# CW340_HyperDebug.net
KiCad netlist of a schematic drawn in Altium Designer
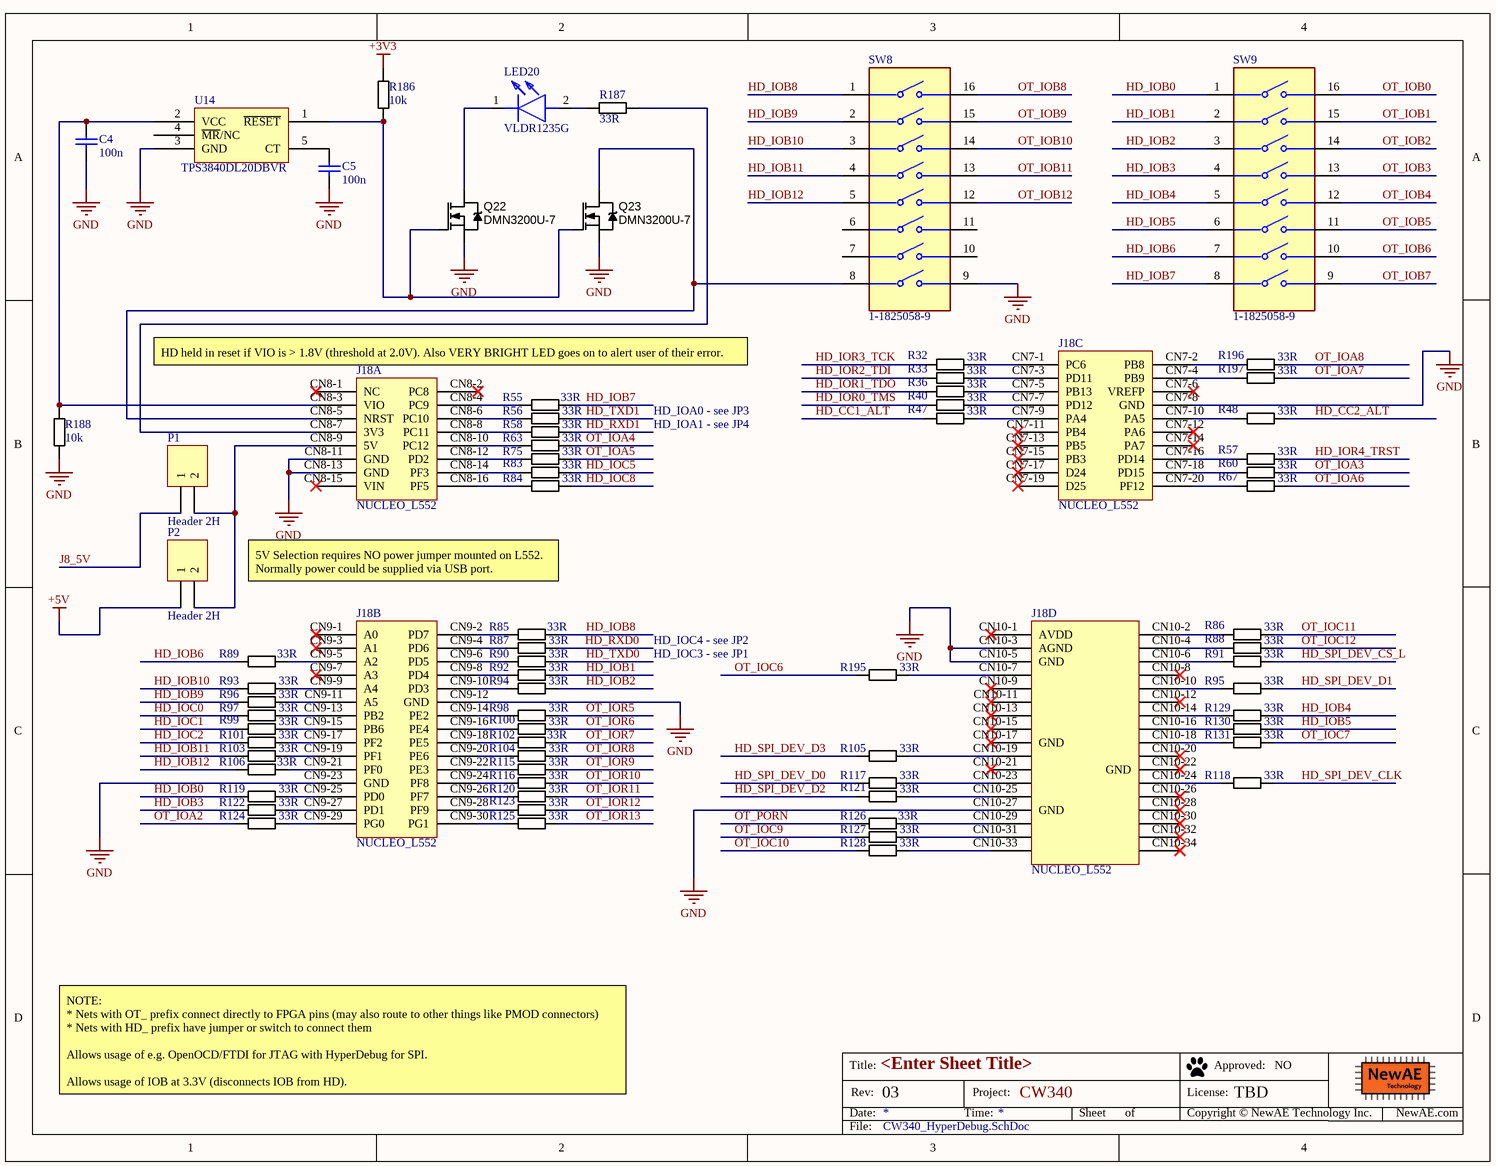
[diagram p0: CW340_HyperDebug.SchDoc]

(export (version "E")
  (design (tool "Eeschema 10.0.6"))
  (components
    (comp (ref "C4")
      (value "100n")
      (footprint "CAPC0402_M")
      (description "100n, 0402")
      (fields (field (name "PART NUMBER") "CCHIP-100n-0402"))
      (libsource (lib "NewAE_AltiumLib") (part "CAP"))
    )
    (comp (ref "C5")
      (value "100n")
      (footprint "CAPC0402_M")
      (description "100n, 0402")
      (fields (field (name "PART NUMBER") "CCHIP-100n-0402"))
      (libsource (lib "NewAE_AltiumLib") (part "CAP"))
    )
    (comp (ref "J18")
      (value "NUCLEO_L552")
      (footprint "NUCLEO-L552ZE")
      (libsource (lib "NewAE_AltiumLib") (part "NUCLEO_L552"))
    )
    (comp (ref "LED20")
      (value "VLDR1235G")
      (footprint "SamacSys:VLDR1235G")
      (description "LED")
      (fields (field (name "MOUSER PART NUMBER") "78-VLDR1235G"))
      (libsource (lib "*") (part "VLDR1235G"))
    )
    (comp (ref "P1")
      (value "Header 2H")
      (footprint "HDR1X2H")
      (description "Header, 2-Pin, Right Angle")
      (fields (field (name "PUBLISHER") "Altium Limited"))
      (libsource (lib "Miscellaneous Connectors") (part "Header 2H"))
    )
    (comp (ref "P2")
      (value "Header 2H")
      (footprint "HDR1X2H")
      (description "Header, 2-Pin, Right Angle")
      (fields (field (name "PUBLISHER") "Altium Limited"))
      (libsource (lib "Miscellaneous Connectors") (part "Header 2H"))
    )
    (comp (ref "Q22")
      (value "DMN3200U-7")
      (footprint "SOT95P245X110-3M")
      (description "MOSFET N-CH 30V 2.2A SOT23-3")
      (libsource (lib "NewAE_AltiumLib") (part "MOSFET_N_GSD"))
    )
    (comp (ref "Q23")
      (value "DMN3200U-7")
      (footprint "SOT95P245X110-3M")
      (description "MOSFET N-CH 30V 2.2A SOT23-3")
      (libsource (lib "NewAE_AltiumLib") (part "MOSFET_N_GSD"))
    )
    (comp (ref "R32")
      (value "33R")
      (footprint "RESC1608X55N")
      (description "33R res, 0603, 1%, 1/10W")
      (fields (field (name "PART NUMBER") "RCHIP-33R-0603") (field (name "TOLERANCE") "1%"))
      (libsource (lib "NewAE_AltiumLib") (part "RES-EU"))
    )
    (comp (ref "R33")
      (value "33R")
      (footprint "RESC1608X55N")
      (description "33R res, 0603, 1%, 1/10W")
      (fields (field (name "PART NUMBER") "RCHIP-33R-0603") (field (name "TOLERANCE") "1%"))
      (libsource (lib "NewAE_AltiumLib") (part "RES-EU"))
    )
    (comp (ref "R36")
      (value "33R")
      (footprint "RESC1608X55N")
      (description "33R res, 0603, 1%, 1/10W")
      (fields (field (name "PART NUMBER") "RCHIP-33R-0603") (field (name "TOLERANCE") "1%"))
      (libsource (lib "NewAE_AltiumLib") (part "RES-EU"))
    )
    (comp (ref "R40")
      (value "33R")
      (footprint "RESC1608X55N")
      (description "33R res, 0603, 1%, 1/10W")
      (fields (field (name "PART NUMBER") "RCHIP-33R-0603") (field (name "TOLERANCE") "1%"))
      (libsource (lib "NewAE_AltiumLib") (part "RES-EU"))
    )
    (comp (ref "R47")
      (value "33R")
      (footprint "RESC1608X55N")
      (description "33R res, 0603, 1%, 1/10W")
      (fields (field (name "PART NUMBER") "RCHIP-33R-0603") (field (name "TOLERANCE") "1%"))
      (libsource (lib "NewAE_AltiumLib") (part "RES-EU"))
    )
    (comp (ref "R48")
      (value "33R")
      (footprint "RESC1608X55N")
      (description "33R res, 0603, 1%, 1/10W")
      (fields (field (name "PART NUMBER") "RCHIP-33R-0603") (field (name "TOLERANCE") "1%"))
      (libsource (lib "NewAE_AltiumLib") (part "RES-EU"))
    )
    (comp (ref "R55")
      (value "33R")
      (footprint "RESC1608X55N")
      (description "33R res, 0603, 1%, 1/10W")
      (fields (field (name "PART NUMBER") "RCHIP-33R-0603") (field (name "TOLERANCE") "1%"))
      (libsource (lib "NewAE_AltiumLib") (part "RES-EU"))
    )
    (comp (ref "R56")
      (value "33R")
      (footprint "RESC1608X55N")
      (description "33R res, 0603, 1%, 1/10W")
      (fields (field (name "PART NUMBER") "RCHIP-33R-0603") (field (name "TOLERANCE") "1%"))
      (libsource (lib "NewAE_AltiumLib") (part "RES-EU"))
    )
    (comp (ref "R57")
      (value "33R")
      (footprint "RESC1608X55N")
      (description "33R res, 0603, 1%, 1/10W")
      (fields (field (name "PART NUMBER") "RCHIP-33R-0603") (field (name "TOLERANCE") "1%"))
      (libsource (lib "NewAE_AltiumLib") (part "RES-EU"))
    )
    (comp (ref "R58")
      (value "33R")
      (footprint "RESC1608X55N")
      (description "33R res, 0603, 1%, 1/10W")
      (fields (field (name "PART NUMBER") "RCHIP-33R-0603") (field (name "TOLERANCE") "1%"))
      (libsource (lib "NewAE_AltiumLib") (part "RES-EU"))
    )
    (comp (ref "R60")
      (value "33R")
      (footprint "RESC1608X55N")
      (description "33R res, 0603, 1%, 1/10W")
      (fields (field (name "PART NUMBER") "RCHIP-33R-0603") (field (name "TOLERANCE") "1%"))
      (libsource (lib "NewAE_AltiumLib") (part "RES-EU"))
    )
    (comp (ref "R63")
      (value "33R")
      (footprint "RESC1608X55N")
      (description "33R res, 0603, 1%, 1/10W")
      (fields (field (name "PART NUMBER") "RCHIP-33R-0603") (field (name "TOLERANCE") "1%"))
      (libsource (lib "NewAE_AltiumLib") (part "RES-EU"))
    )
    (comp (ref "R67")
      (value "33R")
      (footprint "RESC1608X55N")
      (description "33R res, 0603, 1%, 1/10W")
      (fields (field (name "PART NUMBER") "RCHIP-33R-0603") (field (name "TOLERANCE") "1%"))
      (libsource (lib "NewAE_AltiumLib") (part "RES-EU"))
    )
    (comp (ref "R75")
      (value "33R")
      (footprint "RESC1608X55N")
      (description "33R res, 0603, 1%, 1/10W")
      (fields (field (name "PART NUMBER") "RCHIP-33R-0603") (field (name "TOLERANCE") "1%"))
      (libsource (lib "NewAE_AltiumLib") (part "RES-EU"))
    )
    (comp (ref "R83")
      (value "33R")
      (footprint "RESC1608X55N")
      (description "33R res, 0603, 1%, 1/10W")
      (fields (field (name "PART NUMBER") "RCHIP-33R-0603") (field (name "TOLERANCE") "1%"))
      (libsource (lib "NewAE_AltiumLib") (part "RES-EU"))
    )
    (comp (ref "R84")
      (value "33R")
      (footprint "RESC1608X55N")
      (description "33R res, 0603, 1%, 1/10W")
      (fields (field (name "PART NUMBER") "RCHIP-33R-0603") (field (name "TOLERANCE") "1%"))
      (libsource (lib "NewAE_AltiumLib") (part "RES-EU"))
    )
    (comp (ref "R85")
      (value "33R")
      (footprint "RESC1608X55N")
      (description "33R res, 0603, 1%, 1/10W")
      (fields (field (name "PART NUMBER") "RCHIP-33R-0603") (field (name "TOLERANCE") "1%"))
      (libsource (lib "NewAE_AltiumLib") (part "RES-EU"))
    )
    (comp (ref "R86")
      (value "33R")
      (footprint "RESC1608X55N")
      (description "33R res, 0603, 1%, 1/10W")
      (fields (field (name "PART NUMBER") "RCHIP-33R-0603") (field (name "TOLERANCE") "1%"))
      (libsource (lib "NewAE_AltiumLib") (part "RES-EU"))
    )
    (comp (ref "R87")
      (value "33R")
      (footprint "RESC1608X55N")
      (description "33R res, 0603, 1%, 1/10W")
      (fields (field (name "PART NUMBER") "RCHIP-33R-0603") (field (name "TOLERANCE") "1%"))
      (libsource (lib "NewAE_AltiumLib") (part "RES-EU"))
    )
    (comp (ref "R88")
      (value "33R")
      (footprint "RESC1608X55N")
      (description "33R res, 0603, 1%, 1/10W")
      (fields (field (name "PART NUMBER") "RCHIP-33R-0603") (field (name "TOLERANCE") "1%"))
      (libsource (lib "NewAE_AltiumLib") (part "RES-EU"))
    )
    (comp (ref "R89")
      (value "33R")
      (footprint "RESC1608X55N")
      (description "33R res, 0603, 1%, 1/10W")
      (fields (field (name "PART NUMBER") "RCHIP-33R-0603") (field (name "TOLERANCE") "1%"))
      (libsource (lib "NewAE_AltiumLib") (part "RES-EU"))
    )
    (comp (ref "R90")
      (value "33R")
      (footprint "RESC1608X55N")
      (description "33R res, 0603, 1%, 1/10W")
      (fields (field (name "PART NUMBER") "RCHIP-33R-0603") (field (name "TOLERANCE") "1%"))
      (libsource (lib "NewAE_AltiumLib") (part "RES-EU"))
    )
    (comp (ref "R91")
      (value "33R")
      (footprint "RESC1608X55N")
      (description "33R res, 0603, 1%, 1/10W")
      (fields (field (name "PART NUMBER") "RCHIP-33R-0603") (field (name "TOLERANCE") "1%"))
      (libsource (lib "NewAE_AltiumLib") (part "RES-EU"))
    )
    (comp (ref "R92")
      (value "33R")
      (footprint "RESC1608X55N")
      (description "33R res, 0603, 1%, 1/10W")
      (fields (field (name "PART NUMBER") "RCHIP-33R-0603") (field (name "TOLERANCE") "1%"))
      (libsource (lib "NewAE_AltiumLib") (part "RES-EU"))
    )
    (comp (ref "R93")
      (value "33R")
      (footprint "RESC1608X55N")
      (description "33R res, 0603, 1%, 1/10W")
      (fields (field (name "PART NUMBER") "RCHIP-33R-0603") (field (name "TOLERANCE") "1%"))
      (libsource (lib "NewAE_AltiumLib") (part "RES-EU"))
    )
    (comp (ref "R94")
      (value "33R")
      (footprint "RESC1608X55N")
      (description "33R res, 0603, 1%, 1/10W")
      (fields (field (name "PART NUMBER") "RCHIP-33R-0603") (field (name "TOLERANCE") "1%"))
      (libsource (lib "NewAE_AltiumLib") (part "RES-EU"))
    )
    (comp (ref "R95")
      (value "33R")
      (footprint "RESC1608X55N")
      (description "33R res, 0603, 1%, 1/10W")
      (fields (field (name "PART NUMBER") "RCHIP-33R-0603") (field (name "TOLERANCE") "1%"))
      (libsource (lib "NewAE_AltiumLib") (part "RES-EU"))
    )
    (comp (ref "R96")
      (value "33R")
      (footprint "RESC1608X55N")
      (description "33R res, 0603, 1%, 1/10W")
      (fields (field (name "PART NUMBER") "RCHIP-33R-0603") (field (name "TOLERANCE") "1%"))
      (libsource (lib "NewAE_AltiumLib") (part "RES-EU"))
    )
    (comp (ref "R97")
      (value "33R")
      (footprint "RESC1608X55N")
      (description "33R res, 0603, 1%, 1/10W")
      (fields (field (name "PART NUMBER") "RCHIP-33R-0603") (field (name "TOLERANCE") "1%"))
      (libsource (lib "NewAE_AltiumLib") (part "RES-EU"))
    )
    (comp (ref "R98")
      (value "33R")
      (footprint "RESC1608X55N")
      (description "33R res, 0603, 1%, 1/10W")
      (fields (field (name "PART NUMBER") "RCHIP-33R-0603") (field (name "TOLERANCE") "1%"))
      (libsource (lib "NewAE_AltiumLib") (part "RES-EU"))
    )
    (comp (ref "R99")
      (value "33R")
      (footprint "RESC1608X55N")
      (description "33R res, 0603, 1%, 1/10W")
      (fields (field (name "PART NUMBER") "RCHIP-33R-0603") (field (name "TOLERANCE") "1%"))
      (libsource (lib "NewAE_AltiumLib") (part "RES-EU"))
    )
    (comp (ref "R100")
      (value "33R")
      (footprint "RESC1608X55N")
      (description "33R res, 0603, 1%, 1/10W")
      (fields (field (name "PART NUMBER") "RCHIP-33R-0603") (field (name "TOLERANCE") "1%"))
      (libsource (lib "NewAE_AltiumLib") (part "RES-EU"))
    )
    (comp (ref "R101")
      (value "33R")
      (footprint "RESC1608X55N")
      (description "33R res, 0603, 1%, 1/10W")
      (fields (field (name "PART NUMBER") "RCHIP-33R-0603") (field (name "TOLERANCE") "1%"))
      (libsource (lib "NewAE_AltiumLib") (part "RES-EU"))
    )
    (comp (ref "R102")
      (value "33R")
      (footprint "RESC1608X55N")
      (description "33R res, 0603, 1%, 1/10W")
      (fields (field (name "PART NUMBER") "RCHIP-33R-0603") (field (name "TOLERANCE") "1%"))
      (libsource (lib "NewAE_AltiumLib") (part "RES-EU"))
    )
    (comp (ref "R103")
      (value "33R")
      (footprint "RESC1608X55N")
      (description "33R res, 0603, 1%, 1/10W")
      (fields (field (name "PART NUMBER") "RCHIP-33R-0603") (field (name "TOLERANCE") "1%"))
      (libsource (lib "NewAE_AltiumLib") (part "RES-EU"))
    )
    (comp (ref "R104")
      (value "33R")
      (footprint "RESC1608X55N")
      (description "33R res, 0603, 1%, 1/10W")
      (fields (field (name "PART NUMBER") "RCHIP-33R-0603") (field (name "TOLERANCE") "1%"))
      (libsource (lib "NewAE_AltiumLib") (part "RES-EU"))
    )
    (comp (ref "R105")
      (value "33R")
      (footprint "RESC1608X55N")
      (description "33R res, 0603, 1%, 1/10W")
      (fields (field (name "PART NUMBER") "RCHIP-33R-0603") (field (name "TOLERANCE") "1%"))
      (libsource (lib "NewAE_AltiumLib") (part "RES-EU"))
    )
    (comp (ref "R106")
      (value "33R")
      (footprint "RESC1608X55N")
      (description "33R res, 0603, 1%, 1/10W")
      (fields (field (name "PART NUMBER") "RCHIP-33R-0603") (field (name "TOLERANCE") "1%"))
      (libsource (lib "NewAE_AltiumLib") (part "RES-EU"))
    )
    (comp (ref "R115")
      (value "33R")
      (footprint "RESC1608X55N")
      (description "33R res, 0603, 1%, 1/10W")
      (fields (field (name "PART NUMBER") "RCHIP-33R-0603") (field (name "TOLERANCE") "1%"))
      (libsource (lib "NewAE_AltiumLib") (part "RES-EU"))
    )
    (comp (ref "R116")
      (value "33R")
      (footprint "RESC1608X55N")
      (description "33R res, 0603, 1%, 1/10W")
      (fields (field (name "PART NUMBER") "RCHIP-33R-0603") (field (name "TOLERANCE") "1%"))
      (libsource (lib "NewAE_AltiumLib") (part "RES-EU"))
    )
    (comp (ref "R117")
      (value "33R")
      (footprint "RESC1608X55N")
      (description "33R res, 0603, 1%, 1/10W")
      (fields (field (name "PART NUMBER") "RCHIP-33R-0603") (field (name "TOLERANCE") "1%"))
      (libsource (lib "NewAE_AltiumLib") (part "RES-EU"))
    )
    (comp (ref "R118")
      (value "33R")
      (footprint "RESC1608X55N")
      (description "33R res, 0603, 1%, 1/10W")
      (fields (field (name "PART NUMBER") "RCHIP-33R-0603") (field (name "TOLERANCE") "1%"))
      (libsource (lib "NewAE_AltiumLib") (part "RES-EU"))
    )
    (comp (ref "R119")
      (value "33R")
      (footprint "RESC1608X55N")
      (description "33R res, 0603, 1%, 1/10W")
      (fields (field (name "PART NUMBER") "RCHIP-33R-0603") (field (name "TOLERANCE") "1%"))
      (libsource (lib "NewAE_AltiumLib") (part "RES-EU"))
    )
    (comp (ref "R120")
      (value "33R")
      (footprint "RESC1608X55N")
      (description "33R res, 0603, 1%, 1/10W")
      (fields (field (name "PART NUMBER") "RCHIP-33R-0603") (field (name "TOLERANCE") "1%"))
      (libsource (lib "NewAE_AltiumLib") (part "RES-EU"))
    )
    (comp (ref "R121")
      (value "33R")
      (footprint "RESC1608X55N")
      (description "33R res, 0603, 1%, 1/10W")
      (fields (field (name "PART NUMBER") "RCHIP-33R-0603") (field (name "TOLERANCE") "1%"))
      (libsource (lib "NewAE_AltiumLib") (part "RES-EU"))
    )
    (comp (ref "R122")
      (value "33R")
      (footprint "RESC1608X55N")
      (description "33R res, 0603, 1%, 1/10W")
      (fields (field (name "PART NUMBER") "RCHIP-33R-0603") (field (name "TOLERANCE") "1%"))
      (libsource (lib "NewAE_AltiumLib") (part "RES-EU"))
    )
    (comp (ref "R123")
      (value "33R")
      (footprint "RESC1608X55N")
      (description "33R res, 0603, 1%, 1/10W")
      (fields (field (name "PART NUMBER") "RCHIP-33R-0603") (field (name "TOLERANCE") "1%"))
      (libsource (lib "NewAE_AltiumLib") (part "RES-EU"))
    )
    (comp (ref "R124")
      (value "33R")
      (footprint "RESC1608X55N")
      (description "33R res, 0603, 1%, 1/10W")
      (fields (field (name "PART NUMBER") "RCHIP-33R-0603") (field (name "TOLERANCE") "1%"))
      (libsource (lib "NewAE_AltiumLib") (part "RES-EU"))
    )
    (comp (ref "R125")
      (value "33R")
      (footprint "RESC1608X55N")
      (description "33R res, 0603, 1%, 1/10W")
      (fields (field (name "PART NUMBER") "RCHIP-33R-0603") (field (name "TOLERANCE") "1%"))
      (libsource (lib "NewAE_AltiumLib") (part "RES-EU"))
    )
    (comp (ref "R126")
      (value "33R")
      (footprint "RESC1608X55N")
      (description "33R res, 0603, 1%, 1/10W")
      (fields (field (name "PART NUMBER") "RCHIP-33R-0603") (field (name "TOLERANCE") "1%"))
      (libsource (lib "NewAE_AltiumLib") (part "RES-EU"))
    )
    (comp (ref "R127")
      (value "33R")
      (footprint "RESC1608X55N")
      (description "33R res, 0603, 1%, 1/10W")
      (fields (field (name "PART NUMBER") "RCHIP-33R-0603") (field (name "TOLERANCE") "1%"))
      (libsource (lib "NewAE_AltiumLib") (part "RES-EU"))
    )
    (comp (ref "R128")
      (value "33R")
      (footprint "RESC1608X55N")
      (description "33R res, 0603, 1%, 1/10W")
      (fields (field (name "PART NUMBER") "RCHIP-33R-0603") (field (name "TOLERANCE") "1%"))
      (libsource (lib "NewAE_AltiumLib") (part "RES-EU"))
    )
    (comp (ref "R129")
      (value "33R")
      (footprint "RESC1608X55N")
      (description "33R res, 0603, 1%, 1/10W")
      (fields (field (name "PART NUMBER") "RCHIP-33R-0603") (field (name "TOLERANCE") "1%"))
      (libsource (lib "NewAE_AltiumLib") (part "RES-EU"))
    )
    (comp (ref "R130")
      (value "33R")
      (footprint "RESC1608X55N")
      (description "33R res, 0603, 1%, 1/10W")
      (fields (field (name "PART NUMBER") "RCHIP-33R-0603") (field (name "TOLERANCE") "1%"))
      (libsource (lib "NewAE_AltiumLib") (part "RES-EU"))
    )
    (comp (ref "R131")
      (value "33R")
      (footprint "RESC1608X55N")
      (description "33R res, 0603, 1%, 1/10W")
      (fields (field (name "PART NUMBER") "RCHIP-33R-0603") (field (name "TOLERANCE") "1%"))
      (libsource (lib "NewAE_AltiumLib") (part "RES-EU"))
    )
    (comp (ref "R186")
      (value "10k")
      (footprint "RESC1005X40N")
      (description "10k res, 0402, 1%, 1/16W")
      (fields (field (name "PART NUMBER") "RCHIP-10K-0402") (field (name "TOLERANCE") "1%"))
      (libsource (lib "") (part "RES-EU_1"))
    )
    (comp (ref "R187")
      (value "33R")
      (footprint "RESC1608X55N")
      (description "33R res, 0603, 1%, 1/10W")
      (fields (field (name "PART NUMBER") "RCHIP-33R-0603") (field (name "TOLERANCE") "1%"))
      (libsource (lib "NewAE_AltiumLib") (part "RES-EU"))
    )
    (comp (ref "R188")
      (value "10k")
      (footprint "RESC1005X40N")
      (description "10k res, 0402, 1%, 1/16W")
      (fields (field (name "PART NUMBER") "RCHIP-10K-0402") (field (name "TOLERANCE") "1%"))
      (libsource (lib "") (part "RES-EU_1"))
    )
    (comp (ref "R195")
      (value "33R")
      (footprint "RESC1608X55N")
      (description "33R res, 0603, 1%, 1/10W")
      (fields (field (name "PART NUMBER") "RCHIP-33R-0603") (field (name "TOLERANCE") "1%"))
      (libsource (lib "NewAE_AltiumLib") (part "RES-EU"))
    )
    (comp (ref "R196")
      (value "33R")
      (footprint "RESC1608X55N")
      (description "33R res, 0603, 1%, 1/10W")
      (fields (field (name "PART NUMBER") "RCHIP-33R-0603") (field (name "TOLERANCE") "1%"))
      (libsource (lib "NewAE_AltiumLib") (part "RES-EU"))
    )
    (comp (ref "R197")
      (value "33R")
      (footprint "RESC1608X55N")
      (description "33R res, 0603, 1%, 1/10W")
      (fields (field (name "PART NUMBER") "RCHIP-33R-0603") (field (name "TOLERANCE") "1%"))
      (libsource (lib "NewAE_AltiumLib") (part "RES-EU"))
    )
    (comp (ref "SW8")
      (value "1-1825058-9")
      (footprint "FP-1-1825058-9-MFG")
      (description "SWITCH SLIDE DIP SPST 100MA 24V")
      (fields
        (field (name "MANUFACTURER") "TE Connectivity")
        (field (name "OCTOPART") "https://octopart.com/1-1825058-9-te+connectivity-46507285")
      )
      (libsource (lib "Altium Content Vault") (part "88b473189f0daa5e8e83a09a3141fee"))
    )
    (comp (ref "SW9")
      (value "1-1825058-9")
      (footprint "FP-1-1825058-9-MFG")
      (description "SWITCH SLIDE DIP SPST 100MA 24V")
      (fields
        (field (name "MANUFACTURER") "TE Connectivity")
        (field (name "OCTOPART") "https://octopart.com/1-1825058-9-te+connectivity-46507285")
      )
      (libsource (lib "Altium Content Vault") (part "88b473189f0daa5e8e83a09a3141fee"))
    )
    (comp (ref "U14")
      (value "TPS3840DL20DBVR")
      (footprint "SOT23-5P95_285X145L45X40")
      (description "Reset Supervisor")
      (libsource (lib "NewAE_AltiumLib") (part "TPS3840DL"))
    )
  )
  (nets
    (net (code "1") (name "+3V3") (class "Default")
      (node (ref "R186") (pin "1") (pinfunction "1_1") (pintype "passive"))
    )
    (net (code "2") (name "+5V") (class "Default")
      (node (ref "P2") (pin "1") (pinfunction "1_1") (pintype "passive"))
    )
    (net (code "3") (name "/HD_CC1_ALT") (class "Default")
      (node (ref "R47") (pin "1") (pinfunction "1_1") (pintype "passive"))
    )
    (net (code "4") (name "/HD_CC2_ALT") (class "Default")
      (node (ref "R48") (pin "2") (pinfunction "2_2") (pintype "passive"))
    )
    (net (code "5") (name "/HD_IOB0") (class "Default")
      (node (ref "R119") (pin "1") (pinfunction "1_1") (pintype "passive"))
      (node (ref "SW9") (pin "1") (pinfunction "1_1") (pintype "passive"))
    )
    (net (code "6") (name "/HD_IOB1") (class "Default")
      (node (ref "R92") (pin "2") (pinfunction "2_2") (pintype "passive"))
      (node (ref "SW9") (pin "2") (pinfunction "2_2") (pintype "passive"))
    )
    (net (code "7") (name "/HD_IOB2") (class "Default")
      (node (ref "R94") (pin "2") (pinfunction "2_2") (pintype "passive"))
      (node (ref "SW9") (pin "3") (pinfunction "3_3") (pintype "passive"))
    )
    (net (code "8") (name "/HD_IOB3") (class "Default")
      (node (ref "R122") (pin "1") (pinfunction "1_1") (pintype "passive"))
      (node (ref "SW9") (pin "4") (pinfunction "4_4") (pintype "passive"))
    )
    (net (code "9") (name "/HD_IOB4") (class "Default")
      (node (ref "R129") (pin "2") (pinfunction "2_2") (pintype "passive"))
      (node (ref "SW9") (pin "5") (pinfunction "5_5") (pintype "passive"))
    )
    (net (code "10") (name "/HD_IOB5") (class "Default")
      (node (ref "R130") (pin "2") (pinfunction "2_2") (pintype "passive"))
      (node (ref "SW9") (pin "6") (pinfunction "6_6") (pintype "passive"))
    )
    (net (code "11") (name "/HD_IOB6") (class "Default")
      (node (ref "R89") (pin "1") (pinfunction "1_1") (pintype "passive"))
      (node (ref "SW9") (pin "7") (pinfunction "7_7") (pintype "passive"))
    )
    (net (code "12") (name "/HD_IOB7") (class "Default")
      (node (ref "R55") (pin "2") (pinfunction "2_2") (pintype "passive"))
      (node (ref "SW9") (pin "8") (pinfunction "8_8") (pintype "passive"))
    )
    (net (code "13") (name "/HD_IOB8") (class "Default")
      (node (ref "R85") (pin "2") (pinfunction "2_2") (pintype "passive"))
      (node (ref "SW8") (pin "1") (pinfunction "1_1") (pintype "passive"))
    )
    (net (code "14") (name "/HD_IOB9") (class "Default")
      (node (ref "R96") (pin "1") (pinfunction "1_1") (pintype "passive"))
      (node (ref "SW8") (pin "2") (pinfunction "2_2") (pintype "passive"))
    )
    (net (code "15") (name "/HD_IOB10") (class "Default")
      (node (ref "R93") (pin "1") (pinfunction "1_1") (pintype "passive"))
      (node (ref "SW8") (pin "3") (pinfunction "3_3") (pintype "passive"))
    )
    (net (code "16") (name "/HD_IOB11") (class "Default")
      (node (ref "R103") (pin "1") (pinfunction "1_1") (pintype "passive"))
      (node (ref "SW8") (pin "4") (pinfunction "4_4") (pintype "passive"))
    )
    (net (code "17") (name "/HD_IOB12") (class "Default")
      (node (ref "R106") (pin "1") (pinfunction "1_1") (pintype "passive"))
      (node (ref "SW8") (pin "5") (pinfunction "5_5") (pintype "passive"))
    )
    (net (code "18") (name "/HD_IOC0") (class "Default")
      (node (ref "R97") (pin "1") (pinfunction "1_1") (pintype "passive"))
    )
    (net (code "19") (name "/HD_IOC1") (class "Default")
      (node (ref "R99") (pin "1") (pinfunction "1_1") (pintype "passive"))
    )
    (net (code "20") (name "/HD_IOC2") (class "Default")
      (node (ref "R101") (pin "1") (pinfunction "1_1") (pintype "passive"))
    )
    (net (code "21") (name "/HD_IOC5") (class "Default")
      (node (ref "R83") (pin "2") (pinfunction "2_2") (pintype "passive"))
    )
    (net (code "22") (name "/HD_IOC8") (class "Default")
      (node (ref "R84") (pin "2") (pinfunction "2_2") (pintype "passive"))
    )
    (net (code "23") (name "/HD_IOR0_TMS") (class "Default")
      (node (ref "R40") (pin "1") (pinfunction "1_1") (pintype "passive"))
    )
    (net (code "24") (name "/HD_IOR1_TDO") (class "Default")
      (node (ref "R36") (pin "1") (pinfunction "1_1") (pintype "passive"))
    )
    (net (code "25") (name "/HD_IOR2_TDI") (class "Default")
      (node (ref "R33") (pin "1") (pinfunction "1_1") (pintype "passive"))
    )
    (net (code "26") (name "/HD_IOR3_TCK") (class "Default")
      (node (ref "R32") (pin "1") (pinfunction "1_1") (pintype "passive"))
    )
    (net (code "27") (name "/HD_IOR4_TRST") (class "Default")
      (node (ref "R57") (pin "2") (pinfunction "2_2") (pintype "passive"))
    )
    (net (code "28") (name "/HD_RXD0") (class "Default")
      (node (ref "R87") (pin "2") (pinfunction "2_2") (pintype "passive"))
    )
    (net (code "29") (name "/HD_RXD1") (class "Default")
      (node (ref "R58") (pin "2") (pinfunction "2_2") (pintype "passive"))
    )
    (net (code "30") (name "/HD_SPI_DEV_CLK") (class "Default")
      (node (ref "R118") (pin "2") (pinfunction "2_2") (pintype "passive"))
    )
    (net (code "31") (name "/HD_SPI_DEV_CS_L") (class "Default")
      (node (ref "R91") (pin "2") (pinfunction "2_2") (pintype "passive"))
    )
    (net (code "32") (name "/HD_SPI_DEV_D0") (class "Default")
      (node (ref "R117") (pin "1") (pinfunction "1_1") (pintype "passive"))
    )
    (net (code "33") (name "/HD_SPI_DEV_D1") (class "Default")
      (node (ref "R95") (pin "2") (pinfunction "2_2") (pintype "passive"))
    )
    (net (code "34") (name "/HD_SPI_DEV_D2") (class "Default")
      (node (ref "R121") (pin "1") (pinfunction "1_1") (pintype "passive"))
    )
    (net (code "35") (name "/HD_SPI_DEV_D3") (class "Default")
      (node (ref "R105") (pin "1") (pinfunction "1_1") (pintype "passive"))
    )
    (net (code "36") (name "/HD_TXD0") (class "Default")
      (node (ref "R90") (pin "2") (pinfunction "2_2") (pintype "passive"))
    )
    (net (code "37") (name "/HD_TXD1") (class "Default")
      (node (ref "R56") (pin "2") (pinfunction "2_2") (pintype "passive"))
    )
    (net (code "38") (name "/J8_5V") (class "Default")
      (node (ref "P1") (pin "1") (pinfunction "1_1") (pintype "passive"))
    )
    (net (code "39") (name "/OT_IOA2") (class "Default")
      (node (ref "R124") (pin "1") (pinfunction "1_1") (pintype "passive"))
    )
    (net (code "40") (name "/OT_IOA3") (class "Default")
      (node (ref "R60") (pin "2") (pinfunction "2_2") (pintype "passive"))
    )
    (net (code "41") (name "/OT_IOA4") (class "Default")
      (node (ref "R63") (pin "2") (pinfunction "2_2") (pintype "passive"))
    )
    (net (code "42") (name "/OT_IOA5") (class "Default")
      (node (ref "R75") (pin "2") (pinfunction "2_2") (pintype "passive"))
    )
    (net (code "43") (name "/OT_IOA6") (class "Default")
      (node (ref "R67") (pin "2") (pinfunction "2_2") (pintype "passive"))
    )
    (net (code "44") (name "/OT_IOA7") (class "Default")
      (node (ref "R197") (pin "2") (pinfunction "2_2") (pintype "passive"))
    )
    (net (code "45") (name "/OT_IOA8") (class "Default")
      (node (ref "R196") (pin "2") (pinfunction "2_2") (pintype "passive"))
    )
    (net (code "46") (name "/OT_IOB0") (class "Default")
      (node (ref "SW9") (pin "16") (pinfunction "16_16") (pintype "passive"))
    )
    (net (code "47") (name "/OT_IOB1") (class "Default")
      (node (ref "SW9") (pin "15") (pinfunction "15_15") (pintype "passive"))
    )
    (net (code "48") (name "/OT_IOB2") (class "Default")
      (node (ref "SW9") (pin "14") (pinfunction "14_14") (pintype "passive"))
    )
    (net (code "49") (name "/OT_IOB3") (class "Default")
      (node (ref "SW9") (pin "13") (pinfunction "13_13") (pintype "passive"))
    )
    (net (code "50") (name "/OT_IOB4") (class "Default")
      (node (ref "SW9") (pin "12") (pinfunction "12_12") (pintype "passive"))
    )
    (net (code "51") (name "/OT_IOB5") (class "Default")
      (node (ref "SW9") (pin "11") (pinfunction "11_11") (pintype "passive"))
    )
    (net (code "52") (name "/OT_IOB6") (class "Default")
      (node (ref "SW9") (pin "10") (pinfunction "10_10") (pintype "passive"))
    )
    (net (code "53") (name "/OT_IOB7") (class "Default")
      (node (ref "SW9") (pin "9") (pinfunction "9_9") (pintype "passive"))
    )
    (net (code "54") (name "/OT_IOB8") (class "Default")
      (node (ref "SW8") (pin "16") (pinfunction "16_16") (pintype "passive"))
    )
    (net (code "55") (name "/OT_IOB9") (class "Default")
      (node (ref "SW8") (pin "15") (pinfunction "15_15") (pintype "passive"))
    )
    (net (code "56") (name "/OT_IOB10") (class "Default")
      (node (ref "SW8") (pin "14") (pinfunction "14_14") (pintype "passive"))
    )
    (net (code "57") (name "/OT_IOB11") (class "Default")
      (node (ref "SW8") (pin "13") (pinfunction "13_13") (pintype "passive"))
    )
    (net (code "58") (name "/OT_IOB12") (class "Default")
      (node (ref "SW8") (pin "12") (pinfunction "12_12") (pintype "passive"))
    )
    (net (code "59") (name "/OT_IOC6") (class "Default")
      (node (ref "R195") (pin "1") (pinfunction "1_1") (pintype "passive"))
    )
    (net (code "60") (name "/OT_IOC7") (class "Default")
      (node (ref "R131") (pin "2") (pinfunction "2_2") (pintype "passive"))
    )
    (net (code "61") (name "/OT_IOC9") (class "Default")
      (node (ref "R127") (pin "1") (pinfunction "1_1") (pintype "passive"))
    )
    (net (code "62") (name "/OT_IOC10") (class "Default")
      (node (ref "R128") (pin "1") (pinfunction "1_1") (pintype "passive"))
    )
    (net (code "63") (name "/OT_IOC11") (class "Default")
      (node (ref "R86") (pin "2") (pinfunction "2_2") (pintype "passive"))
    )
    (net (code "64") (name "/OT_IOC12") (class "Default")
      (node (ref "R88") (pin "2") (pinfunction "2_2") (pintype "passive"))
    )
    (net (code "65") (name "/OT_IOR5") (class "Default")
      (node (ref "R98") (pin "2") (pinfunction "2_2") (pintype "passive"))
    )
    (net (code "66") (name "/OT_IOR6") (class "Default")
      (node (ref "R100") (pin "2") (pinfunction "2_2") (pintype "passive"))
    )
    (net (code "67") (name "/OT_IOR7") (class "Default")
      (node (ref "R102") (pin "2") (pinfunction "2_2") (pintype "passive"))
    )
    (net (code "68") (name "/OT_IOR8") (class "Default")
      (node (ref "R104") (pin "2") (pinfunction "2_2") (pintype "passive"))
    )
    (net (code "69") (name "/OT_IOR9") (class "Default")
      (node (ref "R115") (pin "2") (pinfunction "2_2") (pintype "passive"))
    )
    (net (code "70") (name "/OT_IOR10") (class "Default")
      (node (ref "R116") (pin "2") (pinfunction "2_2") (pintype "passive"))
    )
    (net (code "71") (name "/OT_IOR11") (class "Default")
      (node (ref "R120") (pin "2") (pinfunction "2_2") (pintype "passive"))
    )
    (net (code "72") (name "/OT_IOR12") (class "Default")
      (node (ref "R123") (pin "2") (pinfunction "2_2") (pintype "passive"))
    )
    (net (code "73") (name "/OT_IOR13") (class "Default")
      (node (ref "R125") (pin "2") (pinfunction "2_2") (pintype "passive"))
    )
    (net (code "74") (name "/OT_PORN") (class "Default")
      (node (ref "R126") (pin "1") (pinfunction "1_1") (pintype "passive"))
    )
    (net (code "75") (name "GND") (class "Default")
      (node (ref "C4") (pin "2") (pinfunction "2_2") (pintype "passive"))
      (node (ref "C5") (pin "2") (pinfunction "2_2") (pintype "passive"))
      (node (ref "J18") (pin "CN10-27") (pinfunction "GND_CN10-27") (pintype "passive"))
      (node (ref "J18") (pin "CN10-3") (pinfunction "AGND_CN10-3") (pintype "passive"))
      (node (ref "J18") (pin "CN10-5") (pinfunction "GND_CN10-5") (pintype "passive"))
      (node (ref "J18") (pin "CN7-8") (pinfunction "GND_CN7-8") (pintype "passive"))
      (node (ref "J18") (pin "CN8-11") (pinfunction "GND_CN8-11") (pintype "passive"))
      (node (ref "J18") (pin "CN8-13") (pinfunction "GND_CN8-13") (pintype "passive"))
      (node (ref "J18") (pin "CN9-12") (pinfunction "GND_CN9-12") (pintype "passive"))
      (node (ref "J18") (pin "CN9-23") (pinfunction "GND_CN9-23") (pintype "passive"))
      (node (ref "Q22") (pin "2") (pinfunction "S_2") (pintype "passive"))
      (node (ref "Q23") (pin "2") (pinfunction "S_2") (pintype "passive"))
      (node (ref "R188") (pin "2") (pinfunction "2_2") (pintype "passive"))
      (node (ref "SW8") (pin "9") (pinfunction "9_9") (pintype "passive"))
      (node (ref "U14") (pin "3") (pinfunction "GND_3") (pintype "passive"))
    )
    (net (code "76") (name "Net-(J18-PadCN10-2)") (class "Default")
      (node (ref "J18") (pin "CN10-2") (pintype "passive"))
      (node (ref "R86") (pin "1") (pinfunction "1_1") (pintype "passive"))
    )
    (net (code "77") (name "Net-(J18-PadCN10-4)") (class "Default")
      (node (ref "J18") (pin "CN10-4") (pintype "passive"))
      (node (ref "R88") (pin "1") (pinfunction "1_1") (pintype "passive"))
    )
    (net (code "78") (name "Net-(J18-PadCN10-6)") (class "Default")
      (node (ref "J18") (pin "CN10-6") (pintype "passive"))
      (node (ref "R91") (pin "1") (pinfunction "1_1") (pintype "passive"))
    )
    (net (code "79") (name "Net-(J18-PadCN10-7)") (class "Default")
      (node (ref "J18") (pin "CN10-7") (pintype "passive"))
      (node (ref "R195") (pin "2") (pinfunction "2_2") (pintype "passive"))
    )
    (net (code "80") (name "Net-(J18-PadCN10-10)") (class "Default")
      (node (ref "J18") (pin "CN10-10") (pintype "passive"))
      (node (ref "R95") (pin "1") (pinfunction "1_1") (pintype "passive"))
    )
    (net (code "81") (name "Net-(J18-PadCN10-14)") (class "Default")
      (node (ref "J18") (pin "CN10-14") (pintype "passive"))
      (node (ref "R129") (pin "1") (pinfunction "1_1") (pintype "passive"))
    )
    (net (code "82") (name "Net-(J18-PadCN10-16)") (class "Default")
      (node (ref "J18") (pin "CN10-16") (pintype "passive"))
      (node (ref "R130") (pin "1") (pinfunction "1_1") (pintype "passive"))
    )
    (net (code "83") (name "Net-(J18-PadCN10-18)") (class "Default")
      (node (ref "J18") (pin "CN10-18") (pintype "passive"))
      (node (ref "R131") (pin "1") (pinfunction "1_1") (pintype "passive"))
    )
    (net (code "84") (name "Net-(J18-PadCN10-19)") (class "Default")
      (node (ref "J18") (pin "CN10-19") (pintype "passive"))
      (node (ref "R105") (pin "2") (pinfunction "2_2") (pintype "passive"))
    )
    (net (code "85") (name "Net-(J18-PadCN10-23)") (class "Default")
      (node (ref "J18") (pin "CN10-23") (pintype "passive"))
      (node (ref "R117") (pin "2") (pinfunction "2_2") (pintype "passive"))
    )
    (net (code "86") (name "Net-(J18-PadCN10-24)") (class "Default")
      (node (ref "J18") (pin "CN10-24") (pintype "passive"))
      (node (ref "R118") (pin "1") (pinfunction "1_1") (pintype "passive"))
    )
    (net (code "87") (name "Net-(J18-PadCN10-25)") (class "Default")
      (node (ref "J18") (pin "CN10-25") (pintype "passive"))
      (node (ref "R121") (pin "2") (pinfunction "2_2") (pintype "passive"))
    )
    (net (code "88") (name "Net-(J18-PadCN10-29)") (class "Default")
      (node (ref "J18") (pin "CN10-29") (pintype "passive"))
      (node (ref "R126") (pin "2") (pinfunction "2_2") (pintype "passive"))
    )
    (net (code "89") (name "Net-(J18-PadCN10-31)") (class "Default")
      (node (ref "J18") (pin "CN10-31") (pintype "passive"))
      (node (ref "R127") (pin "2") (pinfunction "2_2") (pintype "passive"))
    )
    (net (code "90") (name "Net-(J18-PadCN10-33)") (class "Default")
      (node (ref "J18") (pin "CN10-33") (pintype "passive"))
      (node (ref "R128") (pin "2") (pinfunction "2_2") (pintype "passive"))
    )
    (net (code "91") (name "Net-(J18A-3V3)") (class "Default")
      (node (ref "J18") (pin "CN8-7") (pinfunction "3V3_CN8-7") (pintype "passive"))
      (node (ref "R187") (pin "2") (pinfunction "2_2") (pintype "passive"))
    )
    (net (code "92") (name "Net-(J18A-5V)") (class "Default")
      (node (ref "J18") (pin "CN8-9") (pinfunction "5V_CN8-9") (pintype "passive"))
      (node (ref "P1") (pin "2") (pinfunction "2_2") (pintype "passive"))
      (node (ref "P2") (pin "2") (pinfunction "2_2") (pintype "passive"))
    )
    (net (code "93") (name "Net-(J18A-NRST)") (class "Default")
      (node (ref "J18") (pin "CN8-5") (pinfunction "NRST_CN8-5") (pintype "passive"))
      (node (ref "Q23") (pin "3") (pinfunction "D_3") (pintype "passive"))
      (node (ref "SW8") (pin "8") (pinfunction "8_8") (pintype "passive"))
    )
    (net (code "94") (name "Net-(J18A-PC9)") (class "Default")
      (node (ref "J18") (pin "CN8-4") (pinfunction "PC9_CN8-4") (pintype "passive"))
      (node (ref "R55") (pin "1") (pinfunction "1_1") (pintype "passive"))
    )
    (net (code "95") (name "Net-(J18A-PC10)") (class "Default")
      (node (ref "J18") (pin "CN8-6") (pinfunction "PC10_CN8-6") (pintype "passive"))
      (node (ref "R56") (pin "1") (pinfunction "1_1") (pintype "passive"))
    )
    (net (code "96") (name "Net-(J18A-PC11)") (class "Default")
      (node (ref "J18") (pin "CN8-8") (pinfunction "PC11_CN8-8") (pintype "passive"))
      (node (ref "R58") (pin "1") (pinfunction "1_1") (pintype "passive"))
    )
    (net (code "97") (name "Net-(J18A-PC12)") (class "Default")
      (node (ref "J18") (pin "CN8-10") (pinfunction "PC12_CN8-10") (pintype "passive"))
      (node (ref "R63") (pin "1") (pinfunction "1_1") (pintype "passive"))
    )
    (net (code "98") (name "Net-(J18A-PD2)") (class "Default")
      (node (ref "J18") (pin "CN8-12") (pinfunction "PD2_CN8-12") (pintype "passive"))
      (node (ref "R75") (pin "1") (pinfunction "1_1") (pintype "passive"))
    )
    (net (code "99") (name "Net-(J18A-PF3)") (class "Default")
      (node (ref "J18") (pin "CN8-14") (pinfunction "PF3_CN8-14") (pintype "passive"))
      (node (ref "R83") (pin "1") (pinfunction "1_1") (pintype "passive"))
    )
    (net (code "100") (name "Net-(J18A-PF5)") (class "Default")
      (node (ref "J18") (pin "CN8-16") (pinfunction "PF5_CN8-16") (pintype "passive"))
      (node (ref "R84") (pin "1") (pinfunction "1_1") (pintype "passive"))
    )
    (net (code "101") (name "Net-(J18A-VIO)") (class "Default")
      (node (ref "C4") (pin "1") (pinfunction "1_1") (pintype "passive"))
      (node (ref "J18") (pin "CN8-3") (pinfunction "VIO_CN8-3") (pintype "passive"))
      (node (ref "R188") (pin "1") (pinfunction "1_1") (pintype "passive"))
      (node (ref "U14") (pin "2") (pinfunction "VCC_2") (pintype "passive"))
    )
    (net (code "102") (name "Net-(J18B-A2)") (class "Default")
      (node (ref "J18") (pin "CN9-5") (pinfunction "A2_CN9-5") (pintype "passive"))
      (node (ref "R89") (pin "2") (pinfunction "2_2") (pintype "passive"))
    )
    (net (code "103") (name "Net-(J18B-A4)") (class "Default")
      (node (ref "J18") (pin "CN9-9") (pinfunction "A4_CN9-9") (pintype "passive"))
      (node (ref "R93") (pin "2") (pinfunction "2_2") (pintype "passive"))
    )
    (net (code "104") (name "Net-(J18B-A5)") (class "Default")
      (node (ref "J18") (pin "CN9-11") (pinfunction "A5_CN9-11") (pintype "passive"))
      (node (ref "R96") (pin "2") (pinfunction "2_2") (pintype "passive"))
    )
    (net (code "105") (name "Net-(J18B-PB2)") (class "Default")
      (node (ref "J18") (pin "CN9-13") (pinfunction "PB2_CN9-13") (pintype "passive"))
      (node (ref "R97") (pin "2") (pinfunction "2_2") (pintype "passive"))
    )
    (net (code "106") (name "Net-(J18B-PB6)") (class "Default")
      (node (ref "J18") (pin "CN9-15") (pinfunction "PB6_CN9-15") (pintype "passive"))
      (node (ref "R99") (pin "2") (pinfunction "2_2") (pintype "passive"))
    )
    (net (code "107") (name "Net-(J18B-PD0)") (class "Default")
      (node (ref "J18") (pin "CN9-25") (pinfunction "PD0_CN9-25") (pintype "passive"))
      (node (ref "R119") (pin "2") (pinfunction "2_2") (pintype "passive"))
    )
    (net (code "108") (name "Net-(J18B-PD1)") (class "Default")
      (node (ref "J18") (pin "CN9-27") (pinfunction "PD1_CN9-27") (pintype "passive"))
      (node (ref "R122") (pin "2") (pinfunction "2_2") (pintype "passive"))
    )
    (net (code "109") (name "Net-(J18B-PD3)") (class "Default")
      (node (ref "J18") (pin "CN9-10") (pinfunction "PD3_CN9-10") (pintype "passive"))
      (node (ref "R94") (pin "1") (pinfunction "1_1") (pintype "passive"))
    )
    (net (code "110") (name "Net-(J18B-PD4)") (class "Default")
      (node (ref "J18") (pin "CN9-8") (pinfunction "PD4_CN9-8") (pintype "passive"))
      (node (ref "R92") (pin "1") (pinfunction "1_1") (pintype "passive"))
    )
    (net (code "111") (name "Net-(J18B-PD5)") (class "Default")
      (node (ref "J18") (pin "CN9-6") (pinfunction "PD5_CN9-6") (pintype "passive"))
      (node (ref "R90") (pin "1") (pinfunction "1_1") (pintype "passive"))
    )
    (net (code "112") (name "Net-(J18B-PD6)") (class "Default")
      (node (ref "J18") (pin "CN9-4") (pinfunction "PD6_CN9-4") (pintype "passive"))
      (node (ref "R87") (pin "1") (pinfunction "1_1") (pintype "passive"))
    )
    (net (code "113") (name "Net-(J18B-PD7)") (class "Default")
      (node (ref "J18") (pin "CN9-2") (pinfunction "PD7_CN9-2") (pintype "passive"))
      (node (ref "R85") (pin "1") (pinfunction "1_1") (pintype "passive"))
    )
    (net (code "114") (name "Net-(J18B-PE2)") (class "Default")
      (node (ref "J18") (pin "CN9-14") (pinfunction "PE2_CN9-14") (pintype "passive"))
      (node (ref "R98") (pin "1") (pinfunction "1_1") (pintype "passive"))
    )
    (net (code "115") (name "Net-(J18B-PE3)") (class "Default")
      (node (ref "J18") (pin "CN9-22") (pinfunction "PE3_CN9-22") (pintype "passive"))
      (node (ref "R115") (pin "1") (pinfunction "1_1") (pintype "passive"))
    )
    (net (code "116") (name "Net-(J18B-PE4)") (class "Default")
      (node (ref "J18") (pin "CN9-16") (pinfunction "PE4_CN9-16") (pintype "passive"))
      (node (ref "R100") (pin "1") (pinfunction "1_1") (pintype "passive"))
    )
    (net (code "117") (name "Net-(J18B-PE5)") (class "Default")
      (node (ref "J18") (pin "CN9-18") (pinfunction "PE5_CN9-18") (pintype "passive"))
      (node (ref "R102") (pin "1") (pinfunction "1_1") (pintype "passive"))
    )
    (net (code "118") (name "Net-(J18B-PE6)") (class "Default")
      (node (ref "J18") (pin "CN9-20") (pinfunction "PE6_CN9-20") (pintype "passive"))
      (node (ref "R104") (pin "1") (pinfunction "1_1") (pintype "passive"))
    )
    (net (code "119") (name "Net-(J18B-PF0)") (class "Default")
      (node (ref "J18") (pin "CN9-21") (pinfunction "PF0_CN9-21") (pintype "passive"))
      (node (ref "R106") (pin "2") (pinfunction "2_2") (pintype "passive"))
    )
    (net (code "120") (name "Net-(J18B-PF1)") (class "Default")
      (node (ref "J18") (pin "CN9-19") (pinfunction "PF1_CN9-19") (pintype "passive"))
      (node (ref "R103") (pin "2") (pinfunction "2_2") (pintype "passive"))
    )
    (net (code "121") (name "Net-(J18B-PF2)") (class "Default")
      (node (ref "J18") (pin "CN9-17") (pinfunction "PF2_CN9-17") (pintype "passive"))
      (node (ref "R101") (pin "2") (pinfunction "2_2") (pintype "passive"))
    )
    (net (code "122") (name "Net-(J18B-PF7)") (class "Default")
      (node (ref "J18") (pin "CN9-26") (pinfunction "PF7_CN9-26") (pintype "passive"))
      (node (ref "R120") (pin "1") (pinfunction "1_1") (pintype "passive"))
    )
    (net (code "123") (name "Net-(J18B-PF8)") (class "Default")
      (node (ref "J18") (pin "CN9-24") (pinfunction "PF8_CN9-24") (pintype "passive"))
      (node (ref "R116") (pin "1") (pinfunction "1_1") (pintype "passive"))
    )
    (net (code "124") (name "Net-(J18B-PF9)") (class "Default")
      (node (ref "J18") (pin "CN9-28") (pinfunction "PF9_CN9-28") (pintype "passive"))
      (node (ref "R123") (pin "1") (pinfunction "1_1") (pintype "passive"))
    )
    (net (code "125") (name "Net-(J18B-PG0)") (class "Default")
      (node (ref "J18") (pin "CN9-29") (pinfunction "PG0_CN9-29") (pintype "passive"))
      (node (ref "R124") (pin "2") (pinfunction "2_2") (pintype "passive"))
    )
    (net (code "126") (name "Net-(J18B-PG1)") (class "Default")
      (node (ref "J18") (pin "CN9-30") (pinfunction "PG1_CN9-30") (pintype "passive"))
      (node (ref "R125") (pin "1") (pinfunction "1_1") (pintype "passive"))
    )
    (net (code "127") (name "Net-(J18C-PA4)") (class "Default")
      (node (ref "J18") (pin "CN7-9") (pinfunction "PA4_CN7-9") (pintype "passive"))
      (node (ref "R47") (pin "2") (pinfunction "2_2") (pintype "passive"))
    )
    (net (code "128") (name "Net-(J18C-PA5)") (class "Default")
      (node (ref "J18") (pin "CN7-10") (pinfunction "PA5_CN7-10") (pintype "passive"))
      (node (ref "R48") (pin "1") (pinfunction "1_1") (pintype "passive"))
    )
    (net (code "129") (name "Net-(J18C-PB8)") (class "Default")
      (node (ref "J18") (pin "CN7-2") (pinfunction "PB8_CN7-2") (pintype "passive"))
      (node (ref "R196") (pin "1") (pinfunction "1_1") (pintype "passive"))
    )
    (net (code "130") (name "Net-(J18C-PB9)") (class "Default")
      (node (ref "J18") (pin "CN7-4") (pinfunction "PB9_CN7-4") (pintype "passive"))
      (node (ref "R197") (pin "1") (pinfunction "1_1") (pintype "passive"))
    )
    (net (code "131") (name "Net-(J18C-PB13)") (class "Default")
      (node (ref "J18") (pin "CN7-5") (pinfunction "PB13_CN7-5") (pintype "passive"))
      (node (ref "R36") (pin "2") (pinfunction "2_2") (pintype "passive"))
    )
    (net (code "132") (name "Net-(J18C-PC6)") (class "Default")
      (node (ref "J18") (pin "CN7-1") (pinfunction "PC6_CN7-1") (pintype "passive"))
      (node (ref "R32") (pin "2") (pinfunction "2_2") (pintype "passive"))
    )
    (net (code "133") (name "Net-(J18C-PD11)") (class "Default")
      (node (ref "J18") (pin "CN7-3") (pinfunction "PD11_CN7-3") (pintype "passive"))
      (node (ref "R33") (pin "2") (pinfunction "2_2") (pintype "passive"))
    )
    (net (code "134") (name "Net-(J18C-PD12)") (class "Default")
      (node (ref "J18") (pin "CN7-7") (pinfunction "PD12_CN7-7") (pintype "passive"))
      (node (ref "R40") (pin "2") (pinfunction "2_2") (pintype "passive"))
    )
    (net (code "135") (name "Net-(J18C-PD14)") (class "Default")
      (node (ref "J18") (pin "CN7-16") (pinfunction "PD14_CN7-16") (pintype "passive"))
      (node (ref "R57") (pin "1") (pinfunction "1_1") (pintype "passive"))
    )
    (net (code "136") (name "Net-(J18C-PD15)") (class "Default")
      (node (ref "J18") (pin "CN7-18") (pinfunction "PD15_CN7-18") (pintype "passive"))
      (node (ref "R60") (pin "1") (pinfunction "1_1") (pintype "passive"))
    )
    (net (code "137") (name "Net-(J18C-PF12)") (class "Default")
      (node (ref "J18") (pin "CN7-20") (pinfunction "PF12_CN7-20") (pintype "passive"))
      (node (ref "R67") (pin "1") (pinfunction "1_1") (pintype "passive"))
    )
    (net (code "138") (name "Net-(LED20-A)") (class "Default")
      (node (ref "LED20") (pin "2") (pinfunction "A_2") (pintype "passive"))
      (node (ref "R187") (pin "1") (pinfunction "1_1") (pintype "passive"))
    )
    (net (code "139") (name "Net-(LED20-K)") (class "Default")
      (node (ref "LED20") (pin "1") (pinfunction "K_1") (pintype "passive"))
      (node (ref "Q22") (pin "3") (pinfunction "D_3") (pintype "passive"))
    )
    (net (code "140") (name "Net-(Q22-G)") (class "Default")
      (node (ref "Q22") (pin "1") (pinfunction "G_1") (pintype "passive"))
      (node (ref "Q23") (pin "1") (pinfunction "G_1") (pintype "passive"))
      (node (ref "R186") (pin "2") (pinfunction "2_2") (pintype "passive"))
      (node (ref "U14") (pin "1") (pinfunction "~{RESET}_1") (pintype "open_collector"))
    )
    (net (code "141") (name "Net-(U14-CT)") (class "Default")
      (node (ref "C5") (pin "1") (pinfunction "1_1") (pintype "passive"))
      (node (ref "U14") (pin "5") (pinfunction "CT_5") (pintype "passive"))
    )
    (net (code "142") (name "unconnected-(J18-PadCN10-8)") (class "Default")
      (node (ref "J18") (pin "CN10-8") (pintype "passive+no_connect"))
    )
    (net (code "143") (name "unconnected-(J18-PadCN10-9)") (class "Default")
      (node (ref "J18") (pin "CN10-9") (pintype "passive+no_connect"))
    )
    (net (code "144") (name "unconnected-(J18-PadCN10-11)") (class "Default")
      (node (ref "J18") (pin "CN10-11") (pintype "passive+no_connect"))
    )
    (net (code "145") (name "unconnected-(J18-PadCN10-12)") (class "Default")
      (node (ref "J18") (pin "CN10-12") (pintype "passive+no_connect"))
    )
    (net (code "146") (name "unconnected-(J18-PadCN10-13)") (class "Default")
      (node (ref "J18") (pin "CN10-13") (pintype "passive+no_connect"))
    )
    (net (code "147") (name "unconnected-(J18-PadCN10-15)") (class "Default")
      (node (ref "J18") (pin "CN10-15") (pintype "passive+no_connect"))
    )
    (net (code "148") (name "unconnected-(J18-PadCN10-20)") (class "Default")
      (node (ref "J18") (pin "CN10-20") (pintype "passive+no_connect"))
    )
    (net (code "149") (name "unconnected-(J18-PadCN10-21)") (class "Default")
      (node (ref "J18") (pin "CN10-21") (pintype "passive+no_connect"))
    )
    (net (code "150") (name "unconnected-(J18-PadCN10-26)") (class "Default")
      (node (ref "J18") (pin "CN10-26") (pintype "passive+no_connect"))
    )
    (net (code "151") (name "unconnected-(J18-PadCN10-28)") (class "Default")
      (node (ref "J18") (pin "CN10-28") (pintype "passive+no_connect"))
    )
    (net (code "152") (name "unconnected-(J18-PadCN10-30)") (class "Default")
      (node (ref "J18") (pin "CN10-30") (pintype "passive+no_connect"))
    )
    (net (code "153") (name "unconnected-(J18-PadCN10-32)") (class "Default")
      (node (ref "J18") (pin "CN10-32") (pintype "passive+no_connect"))
    )
    (net (code "154") (name "unconnected-(J18-PadCN10-34)") (class "Default")
      (node (ref "J18") (pin "CN10-34") (pintype "passive+no_connect"))
    )
    (net (code "155") (name "unconnected-(J18A-NC-PadCN8-1)") (class "Default")
      (node (ref "J18") (pin "CN8-1") (pinfunction "NC_CN8-1") (pintype "passive+no_connect"))
    )
    (net (code "156") (name "unconnected-(J18A-PC8-PadCN8-2)") (class "Default")
      (node (ref "J18") (pin "CN8-2") (pinfunction "PC8_CN8-2") (pintype "passive+no_connect"))
    )
    (net (code "157") (name "unconnected-(J18A-VIN-PadCN8-15)") (class "Default")
      (node (ref "J18") (pin "CN8-15") (pinfunction "VIN_CN8-15") (pintype "passive+no_connect"))
    )
    (net (code "158") (name "unconnected-(J18B-A0-PadCN9-1)") (class "Default")
      (node (ref "J18") (pin "CN9-1") (pinfunction "A0_CN9-1") (pintype "passive+no_connect"))
    )
    (net (code "159") (name "unconnected-(J18B-A1-PadCN9-3)") (class "Default")
      (node (ref "J18") (pin "CN9-3") (pinfunction "A1_CN9-3") (pintype "passive+no_connect"))
    )
    (net (code "160") (name "unconnected-(J18B-A3-PadCN9-7)") (class "Default")
      (node (ref "J18") (pin "CN9-7") (pinfunction "A3_CN9-7") (pintype "passive+no_connect"))
    )
    (net (code "161") (name "unconnected-(J18C-D24-PadCN7-17)") (class "Default")
      (node (ref "J18") (pin "CN7-17") (pinfunction "D24_CN7-17") (pintype "passive+no_connect"))
    )
    (net (code "162") (name "unconnected-(J18C-D25-PadCN7-19)") (class "Default")
      (node (ref "J18") (pin "CN7-19") (pinfunction "D25_CN7-19") (pintype "passive+no_connect"))
    )
    (net (code "163") (name "unconnected-(J18C-PA6-PadCN7-12)") (class "Default")
      (node (ref "J18") (pin "CN7-12") (pinfunction "PA6_CN7-12") (pintype "passive+no_connect"))
    )
    (net (code "164") (name "unconnected-(J18C-PA7-PadCN7-14)") (class "Default")
      (node (ref "J18") (pin "CN7-14") (pinfunction "PA7_CN7-14") (pintype "passive+no_connect"))
    )
    (net (code "165") (name "unconnected-(J18C-PB3-PadCN7-15)") (class "Default")
      (node (ref "J18") (pin "CN7-15") (pinfunction "PB3_CN7-15") (pintype "passive+no_connect"))
    )
    (net (code "166") (name "unconnected-(J18C-PB4-PadCN7-11)") (class "Default")
      (node (ref "J18") (pin "CN7-11") (pinfunction "PB4_CN7-11") (pintype "passive+no_connect"))
    )
    (net (code "167") (name "unconnected-(J18C-PB5-PadCN7-13)") (class "Default")
      (node (ref "J18") (pin "CN7-13") (pinfunction "PB5_CN7-13") (pintype "passive+no_connect"))
    )
    (net (code "168") (name "unconnected-(J18C-VREFP-PadCN7-6)") (class "Default")
      (node (ref "J18") (pin "CN7-6") (pinfunction "VREFP_CN7-6") (pintype "passive+no_connect"))
    )
    (net (code "169") (name "unconnected-(J18D-AVDD-PadCN10-1)") (class "Default")
      (node (ref "J18") (pin "CN10-1") (pinfunction "AVDD_CN10-1") (pintype "passive+no_connect"))
    )
    (net (code "170") (name "unconnected-(J18D-GND-PadCN10-17)") (class "Default")
      (node (ref "J18") (pin "CN10-17") (pinfunction "GND_CN10-17") (pintype "passive+no_connect"))
    )
    (net (code "171") (name "unconnected-(J18D-GND-PadCN10-22)") (class "Default")
      (node (ref "J18") (pin "CN10-22") (pinfunction "GND_CN10-22") (pintype "passive+no_connect"))
    )
    (net (code "172") (name "unconnected-(SW8-Pad6)") (class "Default")
      (node (ref "SW8") (pin "6") (pinfunction "6_6") (pintype "passive"))
    )
    (net (code "173") (name "unconnected-(SW8-Pad7)") (class "Default")
      (node (ref "SW8") (pin "7") (pinfunction "7_7") (pintype "passive"))
    )
    (net (code "174") (name "unconnected-(SW8-Pad10)") (class "Default")
      (node (ref "SW8") (pin "10") (pinfunction "10_10") (pintype "passive"))
    )
    (net (code "175") (name "unconnected-(SW8-Pad11)") (class "Default")
      (node (ref "SW8") (pin "11") (pinfunction "11_11") (pintype "passive"))
    )
    (net (code "176") (name "unconnected-(U14-~{MR}{slash}NC-Pad4)") (class "Default")
      (node (ref "U14") (pin "4") (pinfunction "~{MR}/NC_4") (pintype "passive"))
    )
  )
)
